# ESP32_Board.net
KiCad netlist of a schematic drawn in Altium Designer
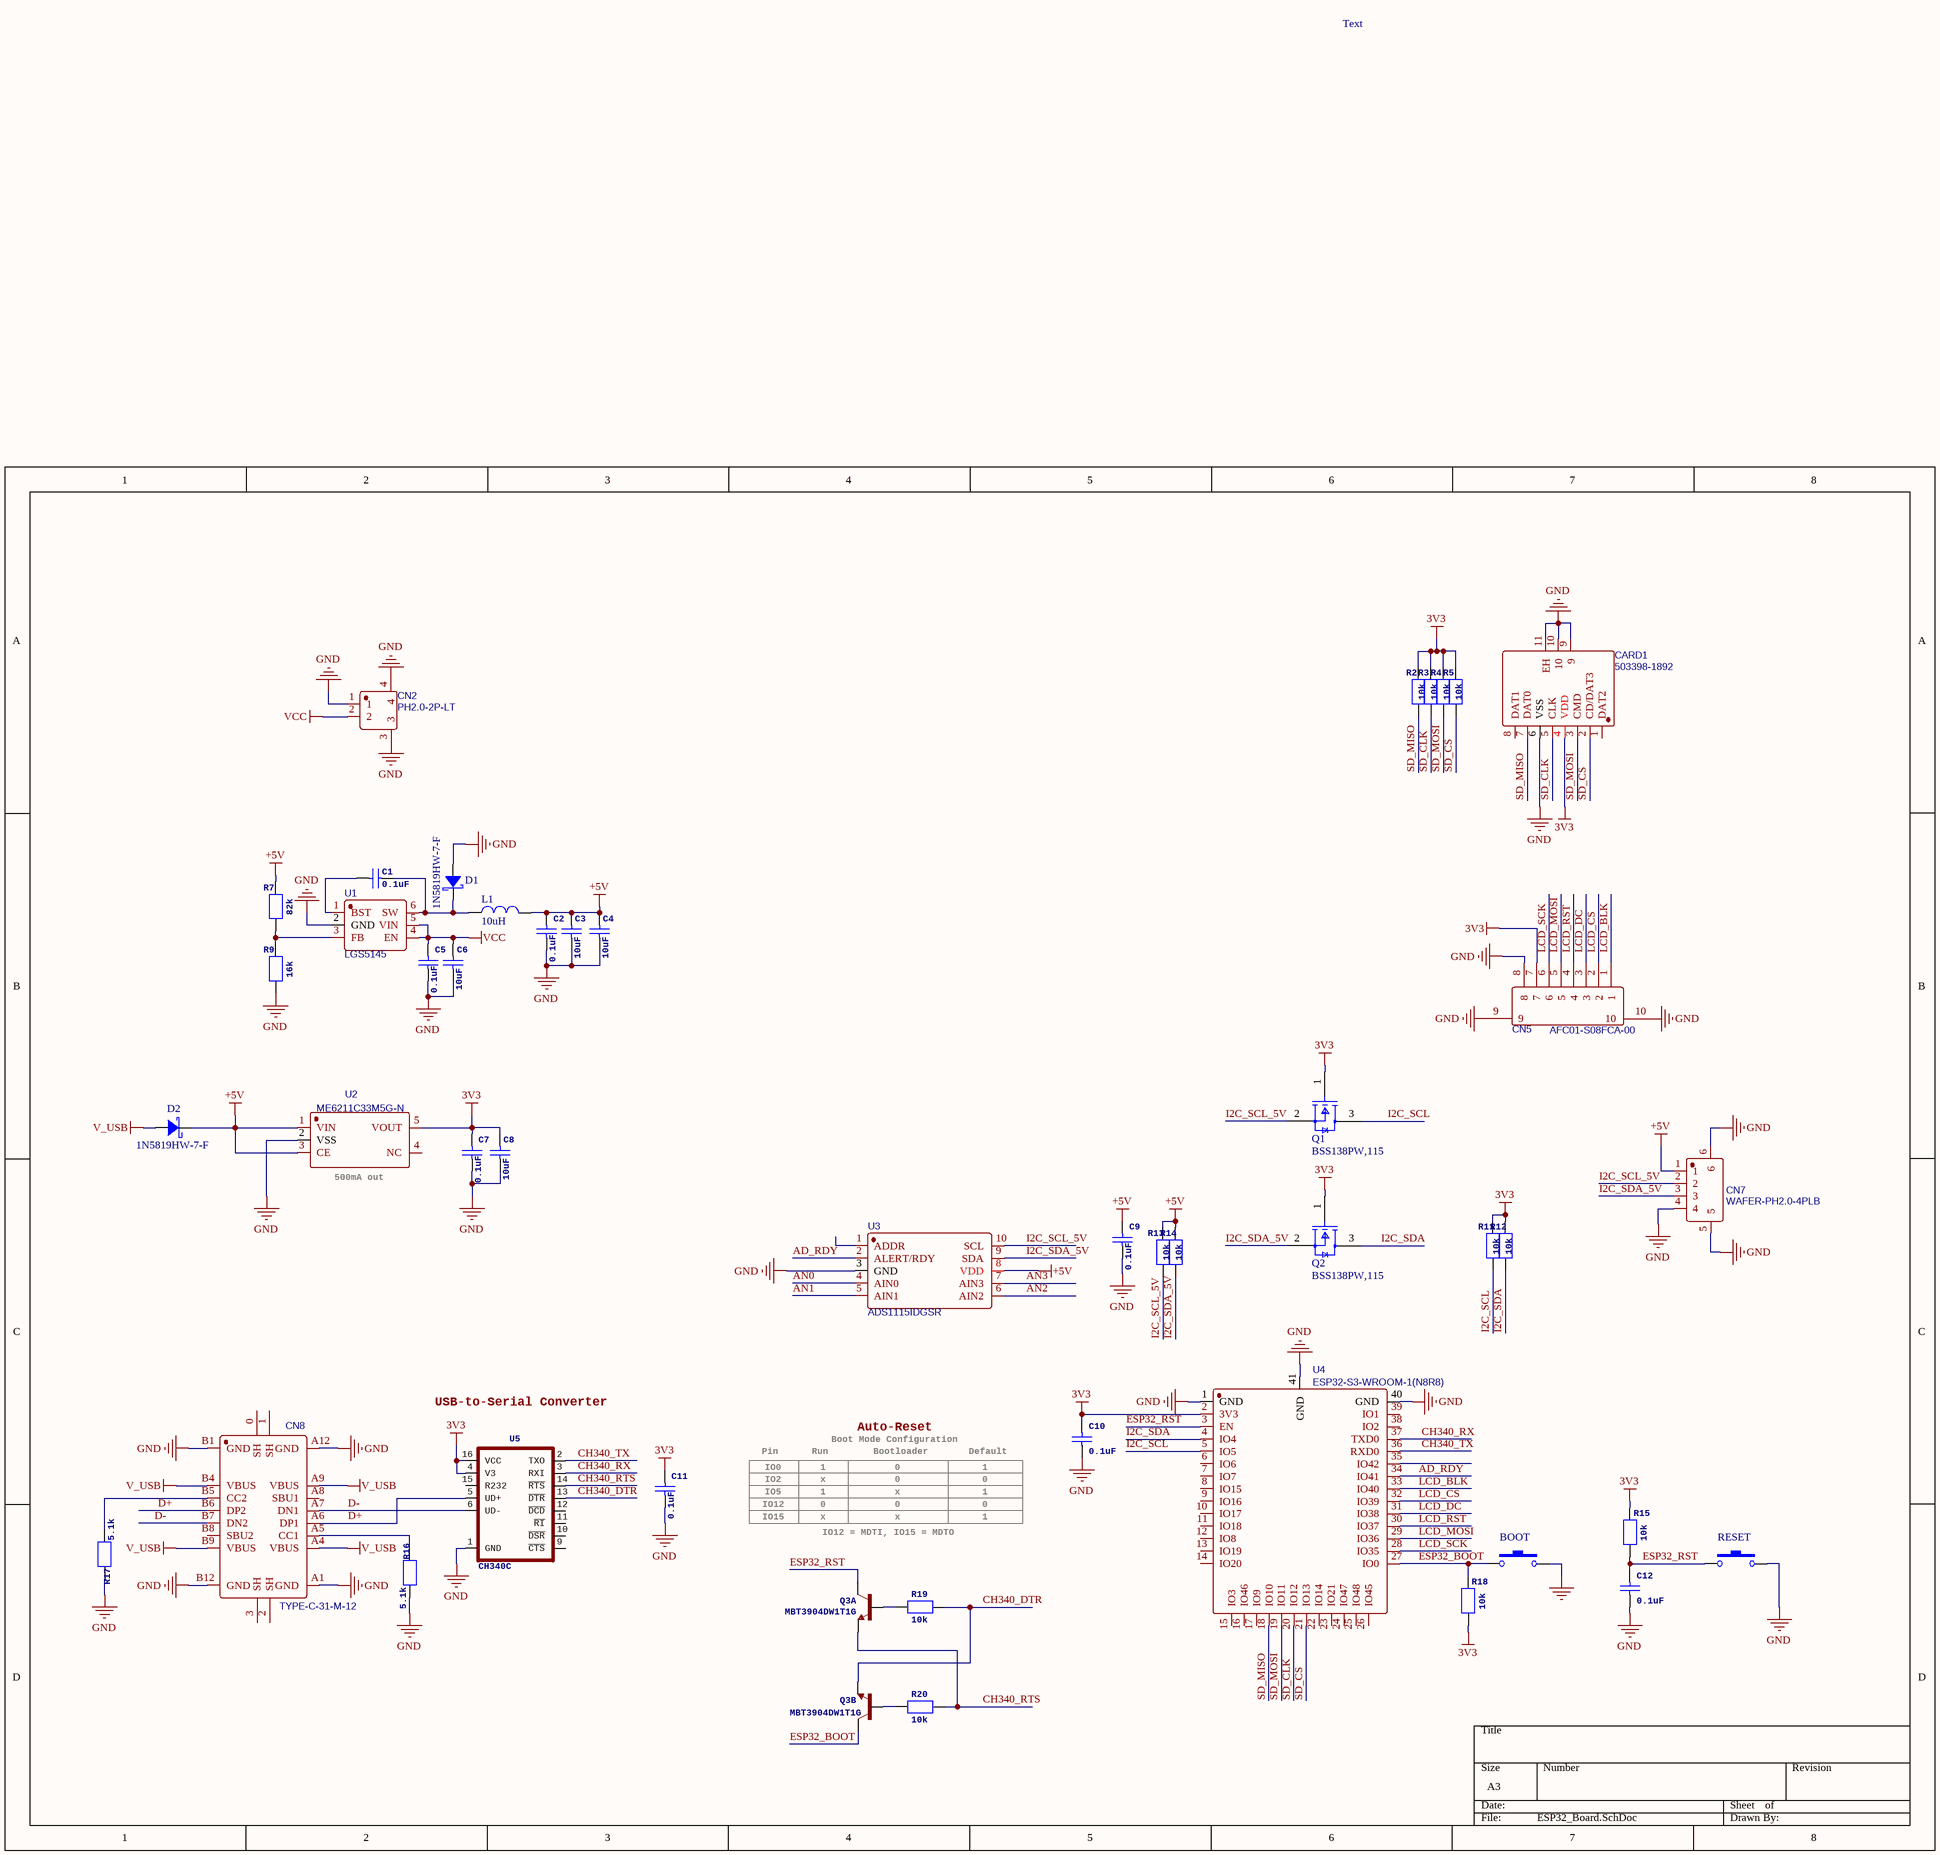
[diagram p0: ESP32_Board.SchDoc]

(export (version "E")
  (design (tool "Eeschema 10.0.6"))
  (components
    (comp (ref "BOOT")
      (value "TS-1088R-02526")
      (footprint "SW-SMD_L3.9-W3.0-P4.45")
      (description "50mA Brick nogging SPST 12V SMD,3x4mm Tactile Switches ROHS")
      (fields (field (name "MANUFACTURER") "XUNPU"))
      (libsource (lib "ESP32_Board") (part "TS-1088R-02526"))
    )
    (comp (ref "C1")
      (value "0.1uF")
      (footprint "C0603")
      (description "0.1uF ± 10% 25V")
      (libsource (lib "ESP32_Board") (part "0.1uF ± 10% 25V"))
    )
    (comp (ref "C2")
      (value "0.1uF")
      (footprint "C0603")
      (description "0.1uF ± 10% 25V")
      (libsource (lib "ESP32_Board") (part "0.1uF ± 10% 25V"))
    )
    (comp (ref "C3")
      (value "10uF")
      (footprint "C1206")
      (description "10uF ± 10% 25V")
      (libsource (lib "ESP32_Board") (part "10uF ± 10% 25V"))
    )
    (comp (ref "C4")
      (value "10uF")
      (footprint "C1206")
      (description "10uF ± 10% 25V")
      (libsource (lib "ESP32_Board") (part "10uF ± 10% 25V"))
    )
    (comp (ref "C5")
      (value "0.1uF")
      (footprint "C0603")
      (description "0.1uF ± 10% 25V")
      (libsource (lib "ESP32_Board") (part "0.1uF ± 10% 25V"))
    )
    (comp (ref "C6")
      (value "10uF")
      (footprint "C1206")
      (description "10uF ± 10% 25V")
      (libsource (lib "ESP32_Board") (part "10uF ± 10% 25V"))
    )
    (comp (ref "C7")
      (value "0.1uF")
      (footprint "C0603")
      (description "0.1uF ± 10% 25V")
      (libsource (lib "ESP32_Board") (part "0.1uF ± 10% 25V"))
    )
    (comp (ref "C8")
      (value "10uF")
      (footprint "C1206")
      (description "10uF ± 10% 25V")
      (libsource (lib "ESP32_Board") (part "10uF ± 10% 25V"))
    )
    (comp (ref "C9")
      (value "0.1uF")
      (footprint "C0603")
      (description "0.1uF ± 10% 25V")
      (libsource (lib "ESP32_Board") (part "0.1uF ± 10% 25V"))
    )
    (comp (ref "C10")
      (value "0.1uF")
      (footprint "C0603")
      (description "0.1uF ± 10% 25V")
      (libsource (lib "ESP32_Board") (part "0.1uF ± 10% 25V"))
    )
    (comp (ref "C11")
      (value "0.1uF")
      (footprint "C0603")
      (description "0.1uF ± 10% 25V")
      (libsource (lib "ESP32_Board") (part "0.1uF ± 10% 25V"))
    )
    (comp (ref "C12")
      (value "0.1uF")
      (footprint "C0603")
      (description "0.1uF ± 10% 25V")
      (libsource (lib "ESP32_Board") (part "0.1uF ± 10% 25V"))
    )
    (comp (ref "CARD1")
      (value "503398-1892")
      (footprint "TF-SMD_503398-1892")
      (description "MicroSD card Connector")
      (fields (field (name "MANUFACTURER") "MOLEX") (field (name "MANUFACTURER PART NUMBER") "5033981892"))
      (libsource (lib "ESP32_Board") (part "503398-1892"))
    )
    (comp (ref "CN2")
      (value "PH2.0-2P-LT")
      (footprint "CONN-SMD_PH2.0-1X2PW")
      (description "1x2P 1 2mm Male pin 2 Brick nogging SMD,P=2mm Wire To Board / Wire To Wire Connector ROHS")
      (fields (field (name "MANUFACTURER") "CAX(创都)"))
      (libsource (lib "ESP32_Board") (part "PH2.0-2P-LT"))
    )
    (comp (ref "CN5")
      (value "AFC01-S08FCA-00")
      (footprint "FPC-SMD_P0.50-8P_FGS-XJ-H2.0")
      (description "Clamshell 8P Bottom Contact Surface Mount 0.5mm SMD,P=0.5mm FFC/FPC Connectors ROHS")
      (fields (field (name "MANUFACTURER") "JS(钜硕电子)"))
      (libsource (lib "ESP32_Board") (part "AFC01-S08FCA-00"))
    )
    (comp (ref "CN7")
      (value "WAFER-PH2.0-4PLB")
      (footprint "CONN-SMD_4P-P2.00_WAFER-200L-4A")
      (fields (field (name "MANUFACTURER") "XUNPU(讯普)"))
      (libsource (lib "altium-import") (part "root_0_WAFER-PH2.0-4PLB_"))
    )
    (comp (ref "CN8")
      (value "TYPE-C-31-M-12")
      (footprint "USB-C_SMD-TYPE-C-31-M-12")
      (description "5A 1 16P Female Type-C SMD USB Connectors ROHS")
      (fields (field (name "MANUFACTURER") "韩国韩荣"))
      (libsource (lib "ESP32_Board") (part "TYPE-C-31-M-12"))
    )
    (comp (ref "D1")
      (value "1N5819HW-7-F")
      (footprint "SOD123")
      (description "40V 450mV@1A 1A SOD-123 Schottky Barrier Diodes (SBD) ROHS")
      (fields (field (name "MANUFACTURER") "Diodes"))
      (libsource (lib "ESP32_Board") (part "1N5819HW-7-F"))
    )
    (comp (ref "D2")
      (value "1N5819HW-7-F")
      (footprint "SOD123")
      (description "40V 450mV@1A 1A SOD-123 Schottky Barrier Diodes (SBD) ROHS")
      (fields (field (name "MANUFACTURER") "Diodes"))
      (libsource (lib "ESP32_Board") (part "1N5819HW-7-F"))
    )
    (comp (ref "L1")
      (value "10uH")
      (footprint "IND-SMD_L4.0-W4.0")
      (description "1.5A 10uH ±20% 2.4A SMD Power Inductors ROHS")
      (fields
        (field (name "MANUFACTURER PART NUMBER") "SWPA4030S100MT")
        (field (name "MANUFACTURER") "Sunlord")
      )
      (libsource (lib "ESP32_Board") (part "1.5A 10uH ±20%"))
    )
    (comp (ref "Q1")
      (value "BSS138PW,115")
      (footprint "Nexperia_SOT323_MFG")
      (description "Trans MOSFET N Channel 50 Volt 0.22A 3-Pin SOT-23 Tape and Reel")
      (fields (field (name "MANUFACTURER") "Nexperia"))
      (libsource (lib "AIB_TekZence_Enviromental") (part "BSS138PW,115"))
    )
    (comp (ref "Q2")
      (value "BSS138PW,115")
      (footprint "Nexperia_SOT323_MFG")
      (description "Trans MOSFET N Channel 50 Volt 0.22A 3-Pin SOT-23 Tape and Reel")
      (fields (field (name "MANUFACTURER") "Nexperia"))
      (libsource (lib "AIB_TekZence_Enviromental") (part "BSS138PW,115"))
    )
    (comp (ref "Q3")
      (value "MBT3904DW1T1G")
      (footprint "SOT-323-6")
      (fields (field (name "MANUFACTURER") "onsemi"))
      (libsource (lib "ESP32_Board") (part "MBT3904DW1T1G"))
    )
    (comp (ref "R2")
      (value "10k")
      (footprint "R0603")
      (description "10 kOhms ±1% 0.1W")
      (libsource (lib "ESP32_Board") (part "10 kOhms ±1% 0.1W"))
    )
    (comp (ref "R3")
      (value "10k")
      (footprint "R0603")
      (description "10 kOhms ±1% 0.1W")
      (libsource (lib "ESP32_Board") (part "10 kOhms ±1% 0.1W"))
    )
    (comp (ref "R4")
      (value "10k")
      (footprint "R0603")
      (description "10 kOhms ±1% 0.1W")
      (libsource (lib "ESP32_Board") (part "10 kOhms ±1% 0.1W"))
    )
    (comp (ref "R5")
      (value "10k")
      (footprint "R0603")
      (description "10 kOhms ±1% 0.1W")
      (libsource (lib "ESP32_Board") (part "10 kOhms ±1% 0.1W"))
    )
    (comp (ref "R7")
      (value "82k")
      (footprint "R0603")
      (description "82 kOhms ±1% 0.1W")
      (libsource (lib "ESP32_Board") (part "82 kOhms ±1% 0.1W"))
    )
    (comp (ref "R9")
      (value "16k")
      (footprint "R0603")
      (description "16 kOhms ±1% 0.1W")
      (libsource (lib "ESP32_Board") (part "16 kOhms ±1% 0.1W"))
    )
    (comp (ref "R11")
      (value "10k")
      (footprint "R0603")
      (description "10 kOhms ±1% 0.1W")
      (libsource (lib "ESP32_Board") (part "10 kOhms ±1% 0.1W"))
    )
    (comp (ref "R12")
      (value "10k")
      (footprint "R0603")
      (description "10 kOhms ±1% 0.1W")
      (libsource (lib "ESP32_Board") (part "10 kOhms ±1% 0.1W"))
    )
    (comp (ref "R13")
      (value "10k")
      (footprint "R0603")
      (description "10 kOhms ±1% 0.1W")
      (libsource (lib "ESP32_Board") (part "10 kOhms ±1% 0.1W"))
    )
    (comp (ref "R14")
      (value "10k")
      (footprint "R0603")
      (description "10 kOhms ±1% 0.1W")
      (libsource (lib "ESP32_Board") (part "10 kOhms ±1% 0.1W"))
    )
    (comp (ref "R15")
      (value "10k")
      (footprint "R0603")
      (description "10 kOhms ±1% 0.1W")
      (libsource (lib "ESP32_Board") (part "10 kOhms ±1% 0.1W"))
    )
    (comp (ref "R16")
      (value "5.1k")
      (footprint "R0603")
      (description "5.1 kOhms ±1% 0.1W")
      (libsource (lib "ESP32_Board") (part "5.1 kOhms ±1% 0.1W"))
    )
    (comp (ref "R17")
      (value "5.1k")
      (footprint "R0603")
      (description "5.1 kOhms ±1% 0.1W")
      (libsource (lib "ESP32_Board") (part "5.1 kOhms ±1% 0.1W"))
    )
    (comp (ref "R18")
      (value "10k")
      (footprint "R0603")
      (description "10 kOhms ±1% 0.1W")
      (libsource (lib "ESP32_Board") (part "10 kOhms ±1% 0.1W"))
    )
    (comp (ref "R19")
      (value "10k")
      (footprint "R0603")
      (description "10 kOhms ±1% 0.1W")
      (libsource (lib "ESP32_Board") (part "10 kOhms ±1% 0.1W"))
    )
    (comp (ref "R20")
      (value "10k")
      (footprint "R0603")
      (description "10 kOhms ±1% 0.1W")
      (libsource (lib "ESP32_Board") (part "10 kOhms ±1% 0.1W"))
    )
    (comp (ref "RESET")
      (value "TS-1088R-02526")
      (footprint "SW-SMD_L3.9-W3.0-P4.45")
      (description "50mA Brick nogging SPST 12V SMD,3x4mm Tactile Switches ROHS")
      (fields (field (name "MANUFACTURER") "XUNPU"))
      (libsource (lib "ESP32_Board") (part "TS-1088R-02526"))
    )
    (comp (ref "U1")
      (value "LGS5145")
      (footprint "SOT-23-6_L2.9-W1.7-P0.95-LS2.8-BL")
      (description "Step-down type Adjustable 1A 0.8V~40V 4.5V~55V SOT-23-6 DC-DC Converters ROHS")
      (fields (field (name "MANUFACTURER") "Legend-Si(棱晶半导体)"))
      (libsource (lib "ESP32_Board") (part "LGS5145"))
    )
    (comp (ref "U2")
      (value "ME6211C33M5G-N")
      (footprint "SOT-23-5_L3.0-W1.7-P0.95-LS2.8-BL")
      (fields (field (name "MANUFACTURER") "MICRONE(南京微盟)"))
      (libsource (lib "altium-import") (part "root_0_ME6211C33M5G-N_"))
    )
    (comp (ref "U3")
      (value "ADS1115IDGSR")
      (footprint "MSOP-10_L3.0-W3.0-P0.50-LS5.0-BL")
      (description "2V~5.5V 16 860Hz I2C VSSOP-10 Analog To Digital Converters (ADCs) ROHS")
      (fields (field (name "MANUFACTURER") "TI"))
      (libsource (lib "ESP32_Board") (part "ADS1115IDGSR"))
    )
    (comp (ref "U4")
      (value "ESP32-S3-WROOM-1(N8R8)")
      (footprint "WIRELM-SMD_ESP32-S3-WROOM-1")
      (description "SMD,18x25.5mm WiFi Modules ROHS")
      (fields (field (name "MANUFACTURER") "ESPRESSIF(乐鑫)"))
      (libsource (lib "ESP32_Board") (part "ESP32-S3-WROOM-1(N8R8)"))
    )
    (comp (ref "U5")
      (value "CH340C")
      (footprint "SOP-16_L10.0-W3.9-P1.27-LS6.0-BL")
      (description "2Mbps Transceiver USB 2.0 SOP-16 USB ICs ROHS")
      (fields (field (name "MANUFACTURER") "WCH"))
      (libsource (lib "ESP32_Board") (part "CH340C"))
    )
  )
  (nets
    (net (code "1") (name "+5V") (class "Default")
      (node (ref "C2") (pin "2") (pinfunction "2_2") (pintype "passive"))
      (node (ref "C3") (pin "2") (pinfunction "2_2") (pintype "passive"))
      (node (ref "C4") (pin "2") (pinfunction "2_2") (pintype "passive"))
      (node (ref "C9") (pin "2") (pinfunction "2_2") (pintype "passive"))
      (node (ref "CN7") (pin "1") (pinfunction "1_1") (pintype "passive"))
      (node (ref "D2") (pin "C") (pinfunction "C_C") (pintype "passive"))
      (node (ref "L1") (pin "2") (pinfunction "2_2") (pintype "passive"))
      (node (ref "R13") (pin "2") (pinfunction "2_2") (pintype "passive"))
      (node (ref "R14") (pin "2") (pinfunction "2_2") (pintype "passive"))
      (node (ref "R7") (pin "2") (pinfunction "2_2") (pintype "passive"))
      (node (ref "U2") (pin "1") (pinfunction "VIN_1") (pintype "passive"))
      (node (ref "U2") (pin "3") (pinfunction "CE_3") (pintype "passive"))
      (node (ref "U3") (pin "8") (pinfunction "VDD_8") (pintype "passive"))
    )
    (net (code "2") (name "/AD_RDY") (class "Default")
      (node (ref "U3") (pin "2") (pinfunction "ALERT/RDY_2") (pintype "passive"))
      (node (ref "U4") (pin "34") (pinfunction "IO41_34") (pintype "passive"))
    )
    (net (code "3") (name "/AN0") (class "Default")
      (node (ref "U3") (pin "4") (pinfunction "AIN0_4") (pintype "passive"))
    )
    (net (code "4") (name "/AN1") (class "Default")
      (node (ref "U3") (pin "5") (pinfunction "AIN1_5") (pintype "passive"))
    )
    (net (code "5") (name "/AN2") (class "Default")
      (node (ref "U3") (pin "6") (pinfunction "AIN2_6") (pintype "passive"))
    )
    (net (code "6") (name "/AN3") (class "Default")
      (node (ref "U3") (pin "7") (pinfunction "AIN3_7") (pintype "passive"))
    )
    (net (code "7") (name "/CH340_DTR") (class "Default")
      (node (ref "Q3") (pin "1") (pinfunction "E_1") (pintype "passive"))
      (node (ref "R19") (pin "1") (pinfunction "1_1") (pintype "passive"))
      (node (ref "U5") (pin "13") (pinfunction "~{DTR}_13") (pintype "passive"))
    )
    (net (code "8") (name "/CH340_RTS") (class "Default")
      (node (ref "Q3") (pin "4") (pinfunction "E_4") (pintype "passive"))
      (node (ref "R20") (pin "1") (pinfunction "1_1") (pintype "passive"))
      (node (ref "U5") (pin "14") (pinfunction "~{RTS}_14") (pintype "passive"))
    )
    (net (code "9") (name "/CH340_RX") (class "Default")
      (node (ref "U4") (pin "37") (pinfunction "TXD0_37") (pintype "passive"))
      (node (ref "U5") (pin "3") (pinfunction "RXI_3") (pintype "passive"))
    )
    (net (code "10") (name "/CH340_TX") (class "Default")
      (node (ref "U4") (pin "36") (pinfunction "RXD0_36") (pintype "passive"))
      (node (ref "U5") (pin "2") (pinfunction "TXO_2") (pintype "passive"))
    )
    (net (code "11") (name "/D+") (class "Default")
      (node (ref "CN8") (pin "A6") (pinfunction "DP1_A6") (pintype "passive"))
      (node (ref "CN8") (pin "B6") (pinfunction "DP2_B6") (pintype "passive"))
      (node (ref "U5") (pin "5") (pinfunction "UD+_5") (pintype "passive"))
    )
    (net (code "12") (name "/D-") (class "Default")
      (node (ref "CN8") (pin "A7") (pinfunction "DN1_A7") (pintype "passive"))
      (node (ref "CN8") (pin "B7") (pinfunction "DN2_B7") (pintype "passive"))
      (node (ref "U5") (pin "6") (pinfunction "UD-_6") (pintype "passive"))
    )
    (net (code "13") (name "/ESP32_BOOT") (class "Default")
      (node (ref "BOOT") (pin "1") (pinfunction "1_1") (pintype "passive"))
      (node (ref "Q3") (pin "6") (pinfunction "C_6") (pintype "passive"))
      (node (ref "R18") (pin "2") (pinfunction "2_2") (pintype "passive"))
      (node (ref "U4") (pin "27") (pinfunction "IO0_27") (pintype "passive"))
    )
    (net (code "14") (name "/ESP32_RST") (class "Default")
      (node (ref "C12") (pin "2") (pinfunction "2_2") (pintype "passive"))
      (node (ref "Q3") (pin "3") (pinfunction "C_3") (pintype "passive"))
      (node (ref "R15") (pin "1") (pinfunction "1_1") (pintype "passive"))
      (node (ref "RESET") (pin "1") (pinfunction "1_1") (pintype "passive"))
      (node (ref "U4") (pin "3") (pinfunction "EN_3") (pintype "passive"))
    )
    (net (code "15") (name "/I2C_SCL") (class "Default")
      (node (ref "Q1") (pin "3") (pinfunction "D_3") (pintype "passive"))
      (node (ref "R11") (pin "1") (pinfunction "1_1") (pintype "passive"))
      (node (ref "U4") (pin "5") (pinfunction "IO5_5") (pintype "passive"))
    )
    (net (code "16") (name "/I2C_SCL_5V") (class "Default")
      (node (ref "CN7") (pin "2") (pinfunction "2_2") (pintype "passive"))
      (node (ref "Q1") (pin "2") (pinfunction "S_2") (pintype "passive"))
      (node (ref "R13") (pin "1") (pinfunction "1_1") (pintype "passive"))
      (node (ref "U3") (pin "10") (pinfunction "SCL_10") (pintype "passive"))
    )
    (net (code "17") (name "/I2C_SDA") (class "Default")
      (node (ref "Q2") (pin "3") (pinfunction "D_3") (pintype "passive"))
      (node (ref "R12") (pin "1") (pinfunction "1_1") (pintype "passive"))
      (node (ref "U4") (pin "4") (pinfunction "IO4_4") (pintype "passive"))
    )
    (net (code "18") (name "/I2C_SDA_5V") (class "Default")
      (node (ref "CN7") (pin "3") (pinfunction "3_3") (pintype "passive"))
      (node (ref "Q2") (pin "2") (pinfunction "S_2") (pintype "passive"))
      (node (ref "R14") (pin "1") (pinfunction "1_1") (pintype "passive"))
      (node (ref "U3") (pin "9") (pinfunction "SDA_9") (pintype "passive"))
    )
    (net (code "19") (name "/LCD_BLK") (class "Default")
      (node (ref "CN5") (pin "1") (pinfunction "1_1") (pintype "passive"))
      (node (ref "U4") (pin "33") (pinfunction "IO40_33") (pintype "passive"))
    )
    (net (code "20") (name "/LCD_CS") (class "Default")
      (node (ref "CN5") (pin "2") (pinfunction "2_2") (pintype "passive"))
      (node (ref "U4") (pin "32") (pinfunction "IO39_32") (pintype "passive"))
    )
    (net (code "21") (name "/LCD_DC") (class "Default")
      (node (ref "CN5") (pin "3") (pinfunction "3_3") (pintype "passive"))
      (node (ref "U4") (pin "31") (pinfunction "IO38_31") (pintype "passive"))
    )
    (net (code "22") (name "/LCD_MOSI") (class "Default")
      (node (ref "CN5") (pin "5") (pinfunction "5_5") (pintype "passive"))
      (node (ref "U4") (pin "29") (pinfunction "IO36_29") (pintype "passive"))
    )
    (net (code "23") (name "/LCD_RST") (class "Default")
      (node (ref "CN5") (pin "4") (pinfunction "4_4") (pintype "passive"))
      (node (ref "U4") (pin "30") (pinfunction "IO37_30") (pintype "passive"))
    )
    (net (code "24") (name "/LCD_SCK") (class "Default")
      (node (ref "CN5") (pin "6") (pinfunction "6_6") (pintype "passive"))
      (node (ref "U4") (pin "28") (pinfunction "IO35_28") (pintype "passive"))
    )
    (net (code "25") (name "/SD_CLK") (class "Default")
      (node (ref "CARD1") (pin "5") (pinfunction "CLK_5") (pintype "passive"))
      (node (ref "R3") (pin "1") (pinfunction "1_1") (pintype "passive"))
      (node (ref "U4") (pin "20") (pinfunction "IO12_20") (pintype "passive"))
    )
    (net (code "26") (name "/SD_CS") (class "Default")
      (node (ref "CARD1") (pin "2") (pinfunction "CD/DAT3_2") (pintype "passive"))
      (node (ref "R5") (pin "1") (pinfunction "1_1") (pintype "passive"))
      (node (ref "U4") (pin "21") (pinfunction "IO13_21") (pintype "passive"))
    )
    (net (code "27") (name "/SD_MISO") (class "Default")
      (node (ref "CARD1") (pin "7") (pinfunction "DAT0_7") (pintype "passive"))
      (node (ref "R2") (pin "1") (pinfunction "1_1") (pintype "passive"))
      (node (ref "U4") (pin "18") (pinfunction "IO10_18") (pintype "passive"))
    )
    (net (code "28") (name "/SD_MOSI") (class "Default")
      (node (ref "CARD1") (pin "3") (pinfunction "CMD_3") (pintype "passive"))
      (node (ref "R4") (pin "1") (pinfunction "1_1") (pintype "passive"))
      (node (ref "U4") (pin "19") (pinfunction "IO11_19") (pintype "passive"))
    )
    (net (code "29") (name "3V3") (class "Default")
      (node (ref "C10") (pin "2") (pinfunction "2_2") (pintype "passive"))
      (node (ref "C11") (pin "2") (pinfunction "2_2") (pintype "passive"))
      (node (ref "C7") (pin "2") (pinfunction "2_2") (pintype "passive"))
      (node (ref "C8") (pin "2") (pinfunction "2_2") (pintype "passive"))
      (node (ref "CARD1") (pin "4") (pinfunction "VDD_4") (pintype "passive"))
      (node (ref "CN5") (pin "7") (pinfunction "7_7") (pintype "passive"))
      (node (ref "Q1") (pin "1") (pinfunction "G_1") (pintype "passive"))
      (node (ref "Q2") (pin "1") (pinfunction "G_1") (pintype "passive"))
      (node (ref "R11") (pin "2") (pinfunction "2_2") (pintype "passive"))
      (node (ref "R12") (pin "2") (pinfunction "2_2") (pintype "passive"))
      (node (ref "R15") (pin "2") (pinfunction "2_2") (pintype "passive"))
      (node (ref "R18") (pin "1") (pinfunction "1_1") (pintype "passive"))
      (node (ref "R2") (pin "2") (pinfunction "2_2") (pintype "passive"))
      (node (ref "R3") (pin "2") (pinfunction "2_2") (pintype "passive"))
      (node (ref "R4") (pin "2") (pinfunction "2_2") (pintype "passive"))
      (node (ref "R5") (pin "2") (pinfunction "2_2") (pintype "passive"))
      (node (ref "U2") (pin "5") (pinfunction "VOUT_5") (pintype "passive"))
      (node (ref "U4") (pin "2") (pinfunction "3V3_2") (pintype "passive"))
      (node (ref "U5") (pin "16") (pinfunction "VCC_16") (pintype "passive"))
      (node (ref "U5") (pin "4") (pinfunction "V3_4") (pintype "passive"))
    )
    (net (code "30") (name "GND") (class "Default")
      (node (ref "BOOT") (pin "2") (pinfunction "2_2") (pintype "passive"))
      (node (ref "C10") (pin "1") (pinfunction "1_1") (pintype "passive"))
      (node (ref "C11") (pin "1") (pinfunction "1_1") (pintype "passive"))
      (node (ref "C12") (pin "1") (pinfunction "1_1") (pintype "passive"))
      (node (ref "C2") (pin "1") (pinfunction "1_1") (pintype "passive"))
      (node (ref "C3") (pin "1") (pinfunction "1_1") (pintype "passive"))
      (node (ref "C4") (pin "1") (pinfunction "1_1") (pintype "passive"))
      (node (ref "C5") (pin "1") (pinfunction "1_1") (pintype "passive"))
      (node (ref "C6") (pin "1") (pinfunction "1_1") (pintype "passive"))
      (node (ref "C7") (pin "1") (pinfunction "1_1") (pintype "passive"))
      (node (ref "C8") (pin "1") (pinfunction "1_1") (pintype "passive"))
      (node (ref "C9") (pin "1") (pinfunction "1_1") (pintype "passive"))
      (node (ref "CARD1") (pin "10") (pinfunction "10_10") (pintype "passive"))
      (node (ref "CARD1") (pin "11") (pinfunction "EH_11") (pintype "passive"))
      (node (ref "CARD1") (pin "6") (pinfunction "VSS_6") (pintype "passive"))
      (node (ref "CARD1") (pin "9") (pinfunction "9_9") (pintype "passive"))
      (node (ref "CN2") (pin "1") (pinfunction "1_1") (pintype "passive"))
      (node (ref "CN2") (pin "3") (pinfunction "3_3") (pintype "passive"))
      (node (ref "CN2") (pin "4") (pinfunction "4_4") (pintype "passive"))
      (node (ref "CN5") (pin "10") (pinfunction "10_10") (pintype "passive"))
      (node (ref "CN5") (pin "8") (pinfunction "8_8") (pintype "passive"))
      (node (ref "CN5") (pin "9") (pinfunction "9_9") (pintype "passive"))
      (node (ref "CN7") (pin "4") (pinfunction "4_4") (pintype "passive"))
      (node (ref "CN7") (pin "5") (pinfunction "5_5") (pintype "passive"))
      (node (ref "CN7") (pin "6") (pinfunction "6_6") (pintype "passive"))
      (node (ref "CN8") (pin "A1") (pinfunction "GND_A1") (pintype "passive"))
      (node (ref "CN8") (pin "A12") (pinfunction "GND_A12") (pintype "passive"))
      (node (ref "CN8") (pin "B1") (pinfunction "GND_B1") (pintype "passive"))
      (node (ref "CN8") (pin "B12") (pinfunction "GND_B12") (pintype "passive"))
      (node (ref "D1") (pin "A") (pinfunction "A_A") (pintype "passive"))
      (node (ref "R16") (pin "1") (pinfunction "1_1") (pintype "passive"))
      (node (ref "R17") (pin "2") (pinfunction "2_2") (pintype "passive"))
      (node (ref "R9") (pin "1") (pinfunction "1_1") (pintype "passive"))
      (node (ref "RESET") (pin "2") (pinfunction "2_2") (pintype "passive"))
      (node (ref "U1") (pin "2") (pinfunction "GND_2") (pintype "passive"))
      (node (ref "U2") (pin "2") (pinfunction "VSS_2") (pintype "passive"))
      (node (ref "U3") (pin "3") (pinfunction "GND_3") (pintype "passive"))
      (node (ref "U4") (pin "1") (pinfunction "GND_1") (pintype "passive"))
      (node (ref "U4") (pin "40") (pinfunction "GND_40") (pintype "passive"))
      (node (ref "U4") (pin "41") (pinfunction "GND_41") (pintype "passive"))
      (node (ref "U5") (pin "1") (pinfunction "GND_1") (pintype "passive"))
    )
    (net (code "31") (name "Net-(CN8-CC1)") (class "Default")
      (node (ref "CN8") (pin "A5") (pinfunction "CC1_A5") (pintype "passive"))
      (node (ref "R16") (pin "2") (pinfunction "2_2") (pintype "passive"))
    )
    (net (code "32") (name "Net-(CN8-CC2)") (class "Default")
      (node (ref "CN8") (pin "B5") (pinfunction "CC2_B5") (pintype "passive"))
      (node (ref "R17") (pin "1") (pinfunction "1_1") (pintype "passive"))
    )
    (net (code "33") (name "Net-(Q3A-B)") (class "Default")
      (node (ref "Q3") (pin "5") (pinfunction "B_5") (pintype "passive"))
      (node (ref "R19") (pin "2") (pinfunction "2_2") (pintype "passive"))
    )
    (net (code "34") (name "Net-(Q3B-B)") (class "Default")
      (node (ref "Q3") (pin "2") (pinfunction "B_2") (pintype "passive"))
      (node (ref "R20") (pin "2") (pinfunction "2_2") (pintype "passive"))
    )
    (net (code "35") (name "Net-(U1-BST)") (class "Default")
      (node (ref "C1") (pin "2") (pinfunction "2_2") (pintype "passive"))
      (node (ref "U1") (pin "1") (pinfunction "BST_1") (pintype "passive"))
    )
    (net (code "36") (name "Net-(U1-FB)") (class "Default")
      (node (ref "R7") (pin "1") (pinfunction "1_1") (pintype "passive"))
      (node (ref "R9") (pin "2") (pinfunction "2_2") (pintype "passive"))
      (node (ref "U1") (pin "3") (pinfunction "FB_3") (pintype "passive"))
    )
    (net (code "37") (name "Net-(U1-SW)") (class "Default")
      (node (ref "C1") (pin "1") (pinfunction "1_1") (pintype "passive"))
      (node (ref "D1") (pin "C") (pinfunction "C_C") (pintype "passive"))
      (node (ref "L1") (pin "1") (pinfunction "1_1") (pintype "passive"))
      (node (ref "U1") (pin "6") (pinfunction "SW_6") (pintype "passive"))
    )
    (net (code "38") (name "VCC") (class "Default")
      (node (ref "C5") (pin "2") (pinfunction "2_2") (pintype "passive"))
      (node (ref "C6") (pin "2") (pinfunction "2_2") (pintype "passive"))
      (node (ref "CN2") (pin "2") (pinfunction "2_2") (pintype "passive"))
      (node (ref "U1") (pin "4") (pinfunction "EN_4") (pintype "passive"))
      (node (ref "U1") (pin "5") (pinfunction "VIN_5") (pintype "passive"))
    )
    (net (code "39") (name "V_USB") (class "Default")
      (node (ref "CN8") (pin "A4") (pinfunction "VBUS_A4") (pintype "passive"))
      (node (ref "CN8") (pin "A9") (pinfunction "VBUS_A9") (pintype "passive"))
      (node (ref "CN8") (pin "B4") (pinfunction "VBUS_B4") (pintype "passive"))
      (node (ref "CN8") (pin "B9") (pinfunction "VBUS_B9") (pintype "passive"))
      (node (ref "D2") (pin "A") (pinfunction "A_A") (pintype "passive"))
    )
    (net (code "40") (name "unconnected-(CARD1-DAT1-Pad8)") (class "Default")
      (node (ref "CARD1") (pin "8") (pinfunction "DAT1_8") (pintype "passive"))
    )
    (net (code "41") (name "unconnected-(CARD1-DAT2-Pad1)") (class "Default")
      (node (ref "CARD1") (pin "1") (pinfunction "DAT2_1") (pintype "passive"))
    )
    (net (code "42") (name "unconnected-(CN8-SBU1-PadA8)") (class "Default")
      (node (ref "CN8") (pin "A8") (pinfunction "SBU1_A8") (pintype "passive"))
    )
    (net (code "43") (name "unconnected-(CN8-SBU2-PadB8)") (class "Default")
      (node (ref "CN8") (pin "B8") (pinfunction "SBU2_B8") (pintype "passive"))
    )
    (net (code "44") (name "unconnected-(CN8-SH-Pad0)") (class "Default")
      (node (ref "CN8") (pin "0") (pinfunction "SH_0") (pintype "passive"))
    )
    (net (code "45") (name "unconnected-(CN8-SH-Pad1)") (class "Default")
      (node (ref "CN8") (pin "1") (pinfunction "SH_1") (pintype "passive"))
    )
    (net (code "46") (name "unconnected-(CN8-SH-Pad2)") (class "Default")
      (node (ref "CN8") (pin "2") (pinfunction "SH_2") (pintype "passive"))
    )
    (net (code "47") (name "unconnected-(CN8-SH-Pad3)") (class "Default")
      (node (ref "CN8") (pin "3") (pinfunction "SH_3") (pintype "passive"))
    )
    (net (code "48") (name "unconnected-(U2-NC-Pad4)") (class "Default")
      (node (ref "U2") (pin "4") (pinfunction "NC_4") (pintype "passive"))
    )
    (net (code "49") (name "unconnected-(U3-ADDR-Pad1)") (class "Default")
      (node (ref "U3") (pin "1") (pinfunction "ADDR_1") (pintype "passive"))
    )
    (net (code "50") (name "unconnected-(U4-IO1-Pad39)") (class "Default")
      (node (ref "U4") (pin "39") (pinfunction "IO1_39") (pintype "passive"))
    )
    (net (code "51") (name "unconnected-(U4-IO2-Pad38)") (class "Default")
      (node (ref "U4") (pin "38") (pinfunction "IO2_38") (pintype "passive"))
    )
    (net (code "52") (name "unconnected-(U4-IO3-Pad15)") (class "Default")
      (node (ref "U4") (pin "15") (pinfunction "IO3_15") (pintype "passive"))
    )
    (net (code "53") (name "unconnected-(U4-IO6-Pad6)") (class "Default")
      (node (ref "U4") (pin "6") (pinfunction "IO6_6") (pintype "passive"))
    )
    (net (code "54") (name "unconnected-(U4-IO7-Pad7)") (class "Default")
      (node (ref "U4") (pin "7") (pinfunction "IO7_7") (pintype "passive"))
    )
    (net (code "55") (name "unconnected-(U4-IO8-Pad12)") (class "Default")
      (node (ref "U4") (pin "12") (pinfunction "IO8_12") (pintype "passive"))
    )
    (net (code "56") (name "unconnected-(U4-IO9-Pad17)") (class "Default")
      (node (ref "U4") (pin "17") (pinfunction "IO9_17") (pintype "passive"))
    )
    (net (code "57") (name "unconnected-(U4-IO14-Pad22)") (class "Default")
      (node (ref "U4") (pin "22") (pinfunction "IO14_22") (pintype "passive"))
    )
    (net (code "58") (name "unconnected-(U4-IO15-Pad8)") (class "Default")
      (node (ref "U4") (pin "8") (pinfunction "IO15_8") (pintype "passive"))
    )
    (net (code "59") (name "unconnected-(U4-IO16-Pad9)") (class "Default")
      (node (ref "U4") (pin "9") (pinfunction "IO16_9") (pintype "passive"))
    )
    (net (code "60") (name "unconnected-(U4-IO17-Pad10)") (class "Default")
      (node (ref "U4") (pin "10") (pinfunction "IO17_10") (pintype "passive"))
    )
    (net (code "61") (name "unconnected-(U4-IO18-Pad11)") (class "Default")
      (node (ref "U4") (pin "11") (pinfunction "IO18_11") (pintype "passive"))
    )
    (net (code "62") (name "unconnected-(U4-IO19-Pad13)") (class "Default")
      (node (ref "U4") (pin "13") (pinfunction "IO19_13") (pintype "passive"))
    )
    (net (code "63") (name "unconnected-(U4-IO20-Pad14)") (class "Default")
      (node (ref "U4") (pin "14") (pinfunction "IO20_14") (pintype "passive"))
    )
    (net (code "64") (name "unconnected-(U4-IO21-Pad23)") (class "Default")
      (node (ref "U4") (pin "23") (pinfunction "IO21_23") (pintype "passive"))
    )
    (net (code "65") (name "unconnected-(U4-IO42-Pad35)") (class "Default")
      (node (ref "U4") (pin "35") (pinfunction "IO42_35") (pintype "passive"))
    )
    (net (code "66") (name "unconnected-(U4-IO45-Pad26)") (class "Default")
      (node (ref "U4") (pin "26") (pinfunction "IO45_26") (pintype "passive"))
    )
    (net (code "67") (name "unconnected-(U4-IO46-Pad16)") (class "Default")
      (node (ref "U4") (pin "16") (pinfunction "IO46_16") (pintype "passive"))
    )
    (net (code "68") (name "unconnected-(U4-IO47-Pad24)") (class "Default")
      (node (ref "U4") (pin "24") (pinfunction "IO47_24") (pintype "passive"))
    )
    (net (code "69") (name "unconnected-(U4-IO48-Pad25)") (class "Default")
      (node (ref "U4") (pin "25") (pinfunction "IO48_25") (pintype "passive"))
    )
    (net (code "70") (name "unconnected-(U5-R232-Pad15)") (class "Default")
      (node (ref "U5") (pin "15") (pinfunction "R232_15") (pintype "passive"))
    )
    (net (code "71") (name "unconnected-(U5-~{CTS}-Pad9)") (class "Default")
      (node (ref "U5") (pin "9") (pinfunction "~{CTS}_9") (pintype "passive"))
    )
    (net (code "72") (name "unconnected-(U5-~{DCD}-Pad12)") (class "Default")
      (node (ref "U5") (pin "12") (pinfunction "~{DCD}_12") (pintype "passive"))
    )
    (net (code "73") (name "unconnected-(U5-~{DSR}-Pad10)") (class "Default")
      (node (ref "U5") (pin "10") (pinfunction "~{DSR}_10") (pintype "passive"))
    )
    (net (code "74") (name "unconnected-(U5-~{RI}-Pad11)") (class "Default")
      (node (ref "U5") (pin "11") (pinfunction "~{RI}_11") (pintype "passive"))
    )
  )
)
